# power.net
KiCad netlist of a schematic drawn in Altium Designer
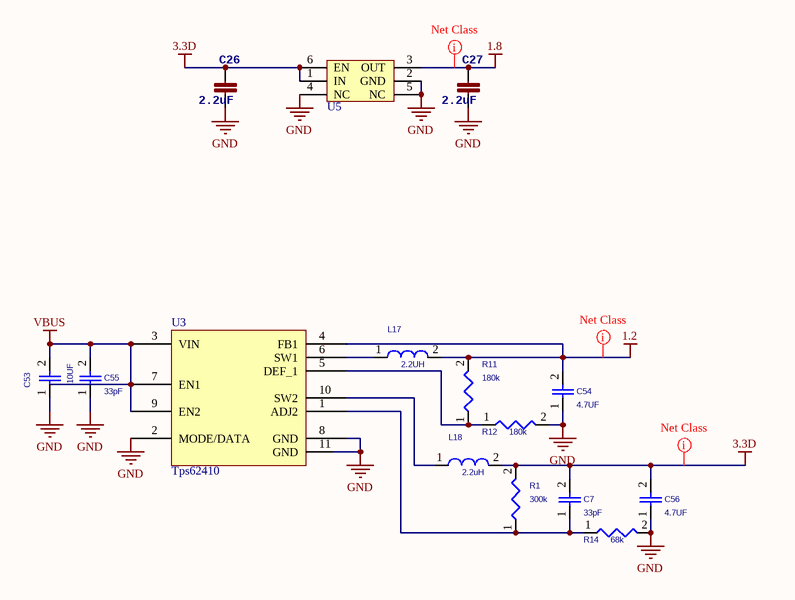
[diagram p0: power.SchDoc]

(export (version "E")
  (design (tool "Eeschema 10.0.6"))
  (components
    (comp (ref "C7") (value "33pF") (footprint "0402") (libsource (lib "*") (part "CAP/0402")))
    (comp (ref "C26")
      (value "2.2uF")
      (footprint "0402")
      (description "<b>Capacitor</b>\nStandard 0603 ceramic capacitor, and 0.1\" leaded capacitor.")
      (fields (field (name "PARTNO") "CC0402ZRY5V7BB104"))
      (libsource (lib "pixhawk2") (part "CAP0402-CAP"))
    )
    (comp (ref "C27")
      (value "2.2uF")
      (footprint "0402")
      (description "<b>Capacitor</b>\nStandard 0603 ceramic capacitor, and 0.1\" leaded capacitor.")
      (fields (field (name "PARTNO") "CC0402ZRY5V7BB104"))
      (libsource (lib "pixhawk2") (part "CAP0402-CAP"))
    )
    (comp (ref "C53") (value "10UF") (footprint "0805") (libsource (lib "*") (part "CAP/0402")))
    (comp (ref "C54") (value "4.7UF") (footprint "0805") (libsource (lib "*") (part "CAP/0402")))
    (comp (ref "C55") (value "33pF") (libsource (lib "*") (part "CAP/0402")))
    (comp (ref "C56") (value "4.7UF") (footprint "0805") (libsource (lib "*") (part "CAP/0402")))
    (comp (ref "L17") (value "2.2UH") (footprint "0806") (libsource (lib "*") (part "L/2.5*2.0")))
    (comp (ref "L18") (value "2.2uH") (footprint "0806") (libsource (lib "*") (part "L/2.5*2.0")))
    (comp (ref "R1") (value "300k") (footprint "0402") (libsource (lib "*") (part "RES/0402_3")))
    (comp (ref "R11") (value "180k") (footprint "0402") (libsource (lib "*") (part "RES/0402_3")))
    (comp (ref "R12") (value "180k") (footprint "0402") (libsource (lib "*") (part "RES/0402_3")))
    (comp (ref "R14") (value "68k") (footprint "0402") (libsource (lib "*") (part "RES/0402_3")))
    (comp (ref "U3") (value "Tps62410") (footprint "DFN-10P-3X3") (libsource (lib "Euler") (part "Tps62410")))
    (comp (ref "U5")
      (value "TLV700xx-WSON")
      (footprint "WSON")
      (libsource (lib "sch") (part "TLV700xx-WSON"))
    )
  )
  (nets
    (net (code "1") (name "1.2") (class "Default")
      (node (ref "C54") (pin "2") (pinfunction "2_2") (pintype "passive"))
      (node (ref "L17") (pin "2") (pinfunction "2_2") (pintype "passive"))
      (node (ref "R11") (pin "2") (pinfunction "2_2") (pintype "passive"))
      (node (ref "U3") (pin "4") (pinfunction "FB1_4") (pintype "passive"))
    )
    (net (code "2") (name "1.8") (class "Default")
      (node (ref "C27") (pin "2") (pinfunction "2_2") (pintype "passive"))
      (node (ref "U5") (pin "3") (pinfunction "OUT_3") (pintype "passive"))
    )
    (net (code "3") (name "3.3D") (class "Default")
      (node (ref "C26") (pin "2") (pinfunction "2_2") (pintype "passive"))
      (node (ref "C56") (pin "2") (pinfunction "2_2") (pintype "passive"))
      (node (ref "C7") (pin "2") (pinfunction "2_2") (pintype "passive"))
      (node (ref "L18") (pin "2") (pinfunction "2_2") (pintype "passive"))
      (node (ref "R1") (pin "2") (pinfunction "2_2") (pintype "passive"))
      (node (ref "U5") (pin "1") (pinfunction "IN_1") (pintype "passive"))
      (node (ref "U5") (pin "6") (pinfunction "EN_6") (pintype "passive"))
    )
    (net (code "4") (name "GND") (class "Default")
      (node (ref "C26") (pin "1") (pinfunction "1_1") (pintype "passive"))
      (node (ref "C27") (pin "1") (pinfunction "1_1") (pintype "passive"))
      (node (ref "C53") (pin "1") (pinfunction "1_1") (pintype "passive"))
      (node (ref "C54") (pin "1") (pinfunction "1_1") (pintype "passive"))
      (node (ref "C55") (pin "1") (pinfunction "1_1") (pintype "passive"))
      (node (ref "C56") (pin "1") (pinfunction "1_1") (pintype "passive"))
      (node (ref "R12") (pin "2") (pinfunction "2_2") (pintype "passive"))
      (node (ref "R14") (pin "2") (pinfunction "2_2") (pintype "passive"))
      (node (ref "U3") (pin "11") (pinfunction "GND_11") (pintype "passive"))
      (node (ref "U3") (pin "2") (pinfunction "MODE/DATA_2") (pintype "passive"))
      (node (ref "U3") (pin "8") (pinfunction "GND_8") (pintype "passive"))
      (node (ref "U5") (pin "2") (pinfunction "GND_2") (pintype "passive"))
      (node (ref "U5") (pin "4") (pinfunction "NC_4") (pintype "passive"))
      (node (ref "U5") (pin "5") (pinfunction "NC_5") (pintype "passive"))
    )
    (net (code "5") (name "Net-(U3-ADJ2)") (class "Default")
      (node (ref "C7") (pin "1") (pinfunction "1_1") (pintype "passive"))
      (node (ref "R1") (pin "1") (pinfunction "1_1") (pintype "passive"))
      (node (ref "R14") (pin "1") (pinfunction "1_1") (pintype "passive"))
      (node (ref "U3") (pin "1") (pinfunction "ADJ2_1") (pintype "passive"))
    )
    (net (code "6") (name "Net-(U3-DEF_1)") (class "Default")
      (node (ref "R11") (pin "1") (pinfunction "1_1") (pintype "passive"))
      (node (ref "R12") (pin "1") (pinfunction "1_1") (pintype "passive"))
      (node (ref "U3") (pin "5") (pinfunction "DEF_1_5") (pintype "passive"))
    )
    (net (code "7") (name "Net-(U3-SW1)") (class "Default")
      (node (ref "L17") (pin "1") (pinfunction "1_1") (pintype "passive"))
      (node (ref "U3") (pin "6") (pinfunction "SW1_6") (pintype "passive"))
    )
    (net (code "8") (name "Net-(U3-SW2)") (class "Default")
      (node (ref "L18") (pin "1") (pinfunction "1_1") (pintype "passive"))
      (node (ref "U3") (pin "10") (pinfunction "SW2_10") (pintype "passive"))
    )
    (net (code "9") (name "VBUS") (class "Default")
      (node (ref "C53") (pin "2") (pinfunction "2_2") (pintype "passive"))
      (node (ref "C55") (pin "2") (pinfunction "2_2") (pintype "passive"))
      (node (ref "U3") (pin "3") (pinfunction "VIN_3") (pintype "passive"))
      (node (ref "U3") (pin "7") (pinfunction "EN1_7") (pintype "passive"))
      (node (ref "U3") (pin "9") (pinfunction "EN2_9") (pintype "passive"))
    )
  )
)
